# taplam.net
KiCad netlist of a schematic drawn in Altium Designer
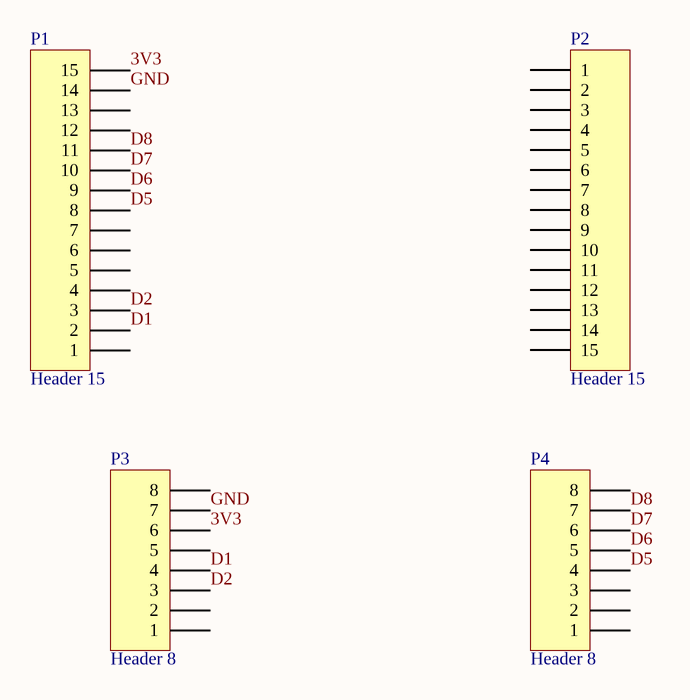
[diagram p0: taplam.SchDoc]

(export (version "E")
  (design (tool "Eeschema 10.0.6"))
  (components
    (comp (ref "P1")
      (value "Header 15")
      (footprint "HDR1X15")
      (description "Header, 15-Pin")
      (fields (field (name "PUBLISHER") "Altium Limited"))
      (libsource (lib "Miscellaneous Connectors") (part "Header 15"))
    )
    (comp (ref "P2")
      (value "Header 15")
      (footprint "HDR1X15")
      (description "Header, 15-Pin")
      (fields (field (name "PUBLISHER") "Altium Limited"))
      (libsource (lib "") (part "Header 15_1"))
    )
    (comp (ref "P3")
      (value "Header 8")
      (footprint "HDR1X8")
      (description "Header, 8-Pin")
      (fields (field (name "PUBLISHER") "Altium Limited"))
      (libsource (lib "Miscellaneous Connectors") (part "Header 8"))
    )
    (comp (ref "P4")
      (value "Header 8")
      (footprint "HDR1X8")
      (description "Header, 8-Pin")
      (fields (field (name "PUBLISHER") "Altium Limited"))
      (libsource (lib "Miscellaneous Connectors") (part "Header 8"))
    )
  )
  (nets
    (net (code "1") (name "/3V3") (class "Default")
      (node (ref "P1") (pin "15") (pinfunction "15_15") (pintype "passive"))
      (node (ref "P3") (pin "6") (pinfunction "6_6") (pintype "passive"))
    )
    (net (code "2") (name "/D1") (class "Default")
      (node (ref "P1") (pin "2") (pinfunction "2_2") (pintype "passive"))
      (node (ref "P3") (pin "4") (pinfunction "4_4") (pintype "passive"))
    )
    (net (code "3") (name "/D2") (class "Default")
      (node (ref "P1") (pin "3") (pinfunction "3_3") (pintype "passive"))
      (node (ref "P3") (pin "3") (pinfunction "3_3") (pintype "passive"))
    )
    (net (code "4") (name "/D5") (class "Default")
      (node (ref "P1") (pin "8") (pinfunction "8_8") (pintype "passive"))
      (node (ref "P4") (pin "4") (pinfunction "4_4") (pintype "passive"))
    )
    (net (code "5") (name "/D6") (class "Default")
      (node (ref "P1") (pin "9") (pinfunction "9_9") (pintype "passive"))
      (node (ref "P4") (pin "5") (pinfunction "5_5") (pintype "passive"))
    )
    (net (code "6") (name "/D7") (class "Default")
      (node (ref "P1") (pin "10") (pinfunction "10_10") (pintype "passive"))
      (node (ref "P4") (pin "6") (pinfunction "6_6") (pintype "passive"))
    )
    (net (code "7") (name "/D8") (class "Default")
      (node (ref "P1") (pin "11") (pinfunction "11_11") (pintype "passive"))
      (node (ref "P4") (pin "7") (pinfunction "7_7") (pintype "passive"))
    )
    (net (code "8") (name "/GND") (class "Default")
      (node (ref "P1") (pin "14") (pinfunction "14_14") (pintype "passive"))
      (node (ref "P3") (pin "7") (pinfunction "7_7") (pintype "passive"))
    )
    (net (code "9") (name "unconnected-(P1-Pad1)") (class "Default")
      (node (ref "P1") (pin "1") (pinfunction "1_1") (pintype "passive"))
    )
    (net (code "10") (name "unconnected-(P1-Pad4)") (class "Default")
      (node (ref "P1") (pin "4") (pinfunction "4_4") (pintype "passive"))
    )
    (net (code "11") (name "unconnected-(P1-Pad5)") (class "Default")
      (node (ref "P1") (pin "5") (pinfunction "5_5") (pintype "passive"))
    )
    (net (code "12") (name "unconnected-(P1-Pad6)") (class "Default")
      (node (ref "P1") (pin "6") (pinfunction "6_6") (pintype "passive"))
    )
    (net (code "13") (name "unconnected-(P1-Pad7)") (class "Default")
      (node (ref "P1") (pin "7") (pinfunction "7_7") (pintype "passive"))
    )
    (net (code "14") (name "unconnected-(P1-Pad12)") (class "Default")
      (node (ref "P1") (pin "12") (pinfunction "12_12") (pintype "passive"))
    )
    (net (code "15") (name "unconnected-(P1-Pad13)") (class "Default")
      (node (ref "P1") (pin "13") (pinfunction "13_13") (pintype "passive"))
    )
    (net (code "16") (name "unconnected-(P2-Pad1)") (class "Default")
      (node (ref "P2") (pin "1") (pinfunction "1_1") (pintype "passive"))
    )
    (net (code "17") (name "unconnected-(P2-Pad2)") (class "Default")
      (node (ref "P2") (pin "2") (pinfunction "2_2") (pintype "passive"))
    )
    (net (code "18") (name "unconnected-(P2-Pad3)") (class "Default")
      (node (ref "P2") (pin "3") (pinfunction "3_3") (pintype "passive"))
    )
    (net (code "19") (name "unconnected-(P2-Pad4)") (class "Default")
      (node (ref "P2") (pin "4") (pinfunction "4_4") (pintype "passive"))
    )
    (net (code "20") (name "unconnected-(P2-Pad5)") (class "Default")
      (node (ref "P2") (pin "5") (pinfunction "5_5") (pintype "passive"))
    )
    (net (code "21") (name "unconnected-(P2-Pad6)") (class "Default")
      (node (ref "P2") (pin "6") (pinfunction "6_6") (pintype "passive"))
    )
    (net (code "22") (name "unconnected-(P2-Pad7)") (class "Default")
      (node (ref "P2") (pin "7") (pinfunction "7_7") (pintype "passive"))
    )
    (net (code "23") (name "unconnected-(P2-Pad8)") (class "Default")
      (node (ref "P2") (pin "8") (pinfunction "8_8") (pintype "passive"))
    )
    (net (code "24") (name "unconnected-(P2-Pad9)") (class "Default")
      (node (ref "P2") (pin "9") (pinfunction "9_9") (pintype "passive"))
    )
    (net (code "25") (name "unconnected-(P2-Pad10)") (class "Default")
      (node (ref "P2") (pin "10") (pinfunction "10_10") (pintype "passive"))
    )
    (net (code "26") (name "unconnected-(P2-Pad11)") (class "Default")
      (node (ref "P2") (pin "11") (pinfunction "11_11") (pintype "passive"))
    )
    (net (code "27") (name "unconnected-(P2-Pad12)") (class "Default")
      (node (ref "P2") (pin "12") (pinfunction "12_12") (pintype "passive"))
    )
    (net (code "28") (name "unconnected-(P2-Pad13)") (class "Default")
      (node (ref "P2") (pin "13") (pinfunction "13_13") (pintype "passive"))
    )
    (net (code "29") (name "unconnected-(P2-Pad14)") (class "Default")
      (node (ref "P2") (pin "14") (pinfunction "14_14") (pintype "passive"))
    )
    (net (code "30") (name "unconnected-(P2-Pad15)") (class "Default")
      (node (ref "P2") (pin "15") (pinfunction "15_15") (pintype "passive"))
    )
    (net (code "31") (name "unconnected-(P3-Pad1)") (class "Default")
      (node (ref "P3") (pin "1") (pinfunction "1_1") (pintype "passive"))
    )
    (net (code "32") (name "unconnected-(P3-Pad2)") (class "Default")
      (node (ref "P3") (pin "2") (pinfunction "2_2") (pintype "passive"))
    )
    (net (code "33") (name "unconnected-(P3-Pad5)") (class "Default")
      (node (ref "P3") (pin "5") (pinfunction "5_5") (pintype "passive"))
    )
    (net (code "34") (name "unconnected-(P3-Pad8)") (class "Default")
      (node (ref "P3") (pin "8") (pinfunction "8_8") (pintype "passive"))
    )
    (net (code "35") (name "unconnected-(P4-Pad1)") (class "Default")
      (node (ref "P4") (pin "1") (pinfunction "1_1") (pintype "passive"))
    )
    (net (code "36") (name "unconnected-(P4-Pad2)") (class "Default")
      (node (ref "P4") (pin "2") (pinfunction "2_2") (pintype "passive"))
    )
    (net (code "37") (name "unconnected-(P4-Pad3)") (class "Default")
      (node (ref "P4") (pin "3") (pinfunction "3_3") (pintype "passive"))
    )
    (net (code "38") (name "unconnected-(P4-Pad8)") (class "Default")
      (node (ref "P4") (pin "8") (pinfunction "8_8") (pintype "passive"))
    )
  )
)
